# MainBoard_TinyK20_RF.net
KiCad netlist of a schematic drawn in Altium Designer
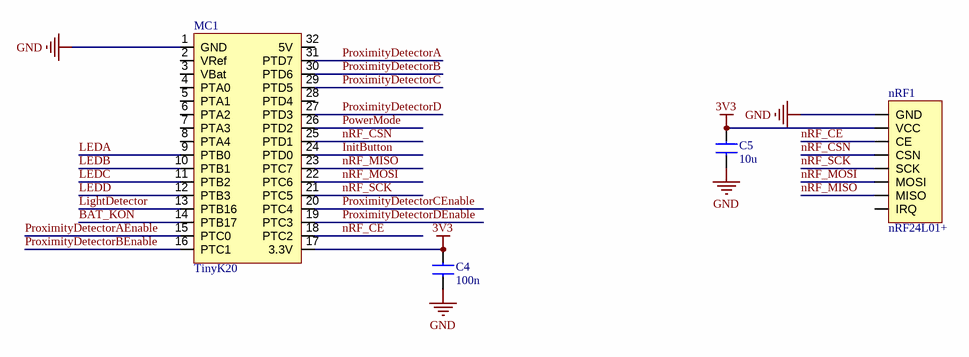
[diagram p0: MainBoard_TinyK20_RF.SchDoc]

(export (version "E")
  (design (tool "Eeschema 10.0.6"))
  (components
    (comp (ref "C4")
      (value "100n")
      (footprint "0805_C")
      (description "Normaler Kondensator")
      (libsource (lib "MainBoard") (part "C?"))
    )
    (comp (ref "C5")
      (value "10u")
      (footprint "0805_C")
      (description "Normaler Kondensator")
      (libsource (lib "MainBoard") (part "C?"))
    )
    (comp (ref "MC1") (value "TinyK20") (footprint "DIP32") (libsource (lib "MainBoard") (part "TinyK20")))
    (comp (ref "nRF1")
      (value "nRF24L01+")
      (footprint "CON_THT_2x4P_RM2.54_Stiftl")
      (libsource (lib "MainBoard") (part "Bluefruit"))
    )
  )
  (nets
    (net (code "1") (name "/BAT_KON") (class "Default")
      (node (ref "MC1") (pin "14") (pinfunction "PTB17_14") (pintype "passive"))
    )
    (net (code "2") (name "/InitButton") (class "Default")
      (node (ref "MC1") (pin "24") (pinfunction "PTD0_24") (pintype "passive"))
    )
    (net (code "3") (name "/LEDA") (class "Default")
      (node (ref "MC1") (pin "9") (pinfunction "PTB0_9") (pintype "passive"))
    )
    (net (code "4") (name "/LEDB") (class "Default")
      (node (ref "MC1") (pin "10") (pinfunction "PTB1_10") (pintype "passive"))
    )
    (net (code "5") (name "/LEDC") (class "Default")
      (node (ref "MC1") (pin "11") (pinfunction "PTB2_11") (pintype "passive"))
    )
    (net (code "6") (name "/LEDD") (class "Default")
      (node (ref "MC1") (pin "12") (pinfunction "PTB3_12") (pintype "passive"))
    )
    (net (code "7") (name "/LightDetector") (class "Default")
      (node (ref "MC1") (pin "13") (pinfunction "PTB16_13") (pintype "passive"))
    )
    (net (code "8") (name "/PowerMode") (class "Default")
      (node (ref "MC1") (pin "26") (pinfunction "PTD2_26") (pintype "passive"))
    )
    (net (code "9") (name "/ProximityDetectorA") (class "Default")
      (node (ref "MC1") (pin "31") (pinfunction "PTD7_31") (pintype "passive"))
    )
    (net (code "10") (name "/ProximityDetectorAEnable") (class "Default")
      (node (ref "MC1") (pin "15") (pinfunction "PTC0_15") (pintype "passive"))
    )
    (net (code "11") (name "/ProximityDetectorB") (class "Default")
      (node (ref "MC1") (pin "30") (pinfunction "PTD6_30") (pintype "passive"))
    )
    (net (code "12") (name "/ProximityDetectorBEnable") (class "Default")
      (node (ref "MC1") (pin "16") (pinfunction "PTC1_16") (pintype "passive"))
    )
    (net (code "13") (name "/ProximityDetectorC") (class "Default")
      (node (ref "MC1") (pin "29") (pinfunction "PTD5_29") (pintype "passive"))
    )
    (net (code "14") (name "/ProximityDetectorCEnable") (class "Default")
      (node (ref "MC1") (pin "20") (pinfunction "PTC4_20") (pintype "passive"))
    )
    (net (code "15") (name "/ProximityDetectorD") (class "Default")
      (node (ref "MC1") (pin "27") (pinfunction "PTD3_27") (pintype "passive"))
    )
    (net (code "16") (name "/ProximityDetectorDEnable") (class "Default")
      (node (ref "MC1") (pin "19") (pinfunction "PTC3_19") (pintype "passive"))
    )
    (net (code "17") (name "/nRF_CE") (class "Default")
      (node (ref "MC1") (pin "18") (pinfunction "PTC2_18") (pintype "passive"))
      (node (ref "nRF1") (pin "3") (pinfunction "CE_3") (pintype "passive"))
    )
    (net (code "18") (name "/nRF_CSN") (class "Default")
      (node (ref "MC1") (pin "25") (pinfunction "PTD1_25") (pintype "passive"))
      (node (ref "nRF1") (pin "4") (pinfunction "CSN_4") (pintype "passive"))
    )
    (net (code "19") (name "/nRF_MISO") (class "Default")
      (node (ref "MC1") (pin "23") (pinfunction "PTC7_23") (pintype "passive"))
      (node (ref "nRF1") (pin "7") (pinfunction "MISO_7") (pintype "passive"))
    )
    (net (code "20") (name "/nRF_MOSI") (class "Default")
      (node (ref "MC1") (pin "22") (pinfunction "PTC6_22") (pintype "passive"))
      (node (ref "nRF1") (pin "6") (pinfunction "MOSI_6") (pintype "passive"))
    )
    (net (code "21") (name "/nRF_SCK") (class "Default")
      (node (ref "MC1") (pin "21") (pinfunction "PTC5_21") (pintype "passive"))
      (node (ref "nRF1") (pin "5") (pinfunction "SCK_5") (pintype "passive"))
    )
    (net (code "22") (name "3V3") (class "Default")
      (node (ref "C4") (pin "2") (pinfunction "2_2") (pintype "passive"))
      (node (ref "C5") (pin "2") (pinfunction "2_2") (pintype "passive"))
      (node (ref "MC1") (pin "17") (pinfunction "3.3V_17") (pintype "passive"))
      (node (ref "nRF1") (pin "2") (pinfunction "VCC_2") (pintype "passive"))
    )
    (net (code "23") (name "GND") (class "Default")
      (node (ref "C4") (pin "1") (pinfunction "1_1") (pintype "passive"))
      (node (ref "C5") (pin "1") (pinfunction "1_1") (pintype "passive"))
      (node (ref "MC1") (pin "1") (pinfunction "GND_1") (pintype "passive"))
      (node (ref "nRF1") (pin "1") (pinfunction "GND_1") (pintype "passive"))
    )
    (net (code "24") (name "unconnected-(MC1-5V-Pad32)") (class "Default")
      (node (ref "MC1") (pin "32") (pinfunction "5V_32") (pintype "passive"))
    )
    (net (code "25") (name "unconnected-(MC1-PTA0-Pad4)") (class "Default")
      (node (ref "MC1") (pin "4") (pinfunction "PTA0_4") (pintype "passive"))
    )
    (net (code "26") (name "unconnected-(MC1-PTA1-Pad5)") (class "Default")
      (node (ref "MC1") (pin "5") (pinfunction "PTA1_5") (pintype "passive"))
    )
    (net (code "27") (name "unconnected-(MC1-PTA2-Pad6)") (class "Default")
      (node (ref "MC1") (pin "6") (pinfunction "PTA2_6") (pintype "passive"))
    )
    (net (code "28") (name "unconnected-(MC1-PTA3-Pad7)") (class "Default")
      (node (ref "MC1") (pin "7") (pinfunction "PTA3_7") (pintype "passive"))
    )
    (net (code "29") (name "unconnected-(MC1-PTA4-Pad8)") (class "Default")
      (node (ref "MC1") (pin "8") (pinfunction "PTA4_8") (pintype "passive"))
    )
    (net (code "30") (name "unconnected-(MC1-PTD4-Pad28)") (class "Default")
      (node (ref "MC1") (pin "28") (pinfunction "PTD4_28") (pintype "passive"))
    )
    (net (code "31") (name "unconnected-(MC1-VBat-Pad3)") (class "Default")
      (node (ref "MC1") (pin "3") (pinfunction "VBat_3") (pintype "passive"))
    )
    (net (code "32") (name "unconnected-(MC1-VRef-Pad2)") (class "Default")
      (node (ref "MC1") (pin "2") (pinfunction "VRef_2") (pintype "passive"))
    )
    (net (code "33") (name "unconnected-(nRF1-IRQ-Pad8)") (class "Default")
      (node (ref "nRF1") (pin "8") (pinfunction "IRQ_8") (pintype "passive"))
    )
  )
)
